# EgyptATTINY44.net
KiCad netlist of a schematic drawn in EAGLE
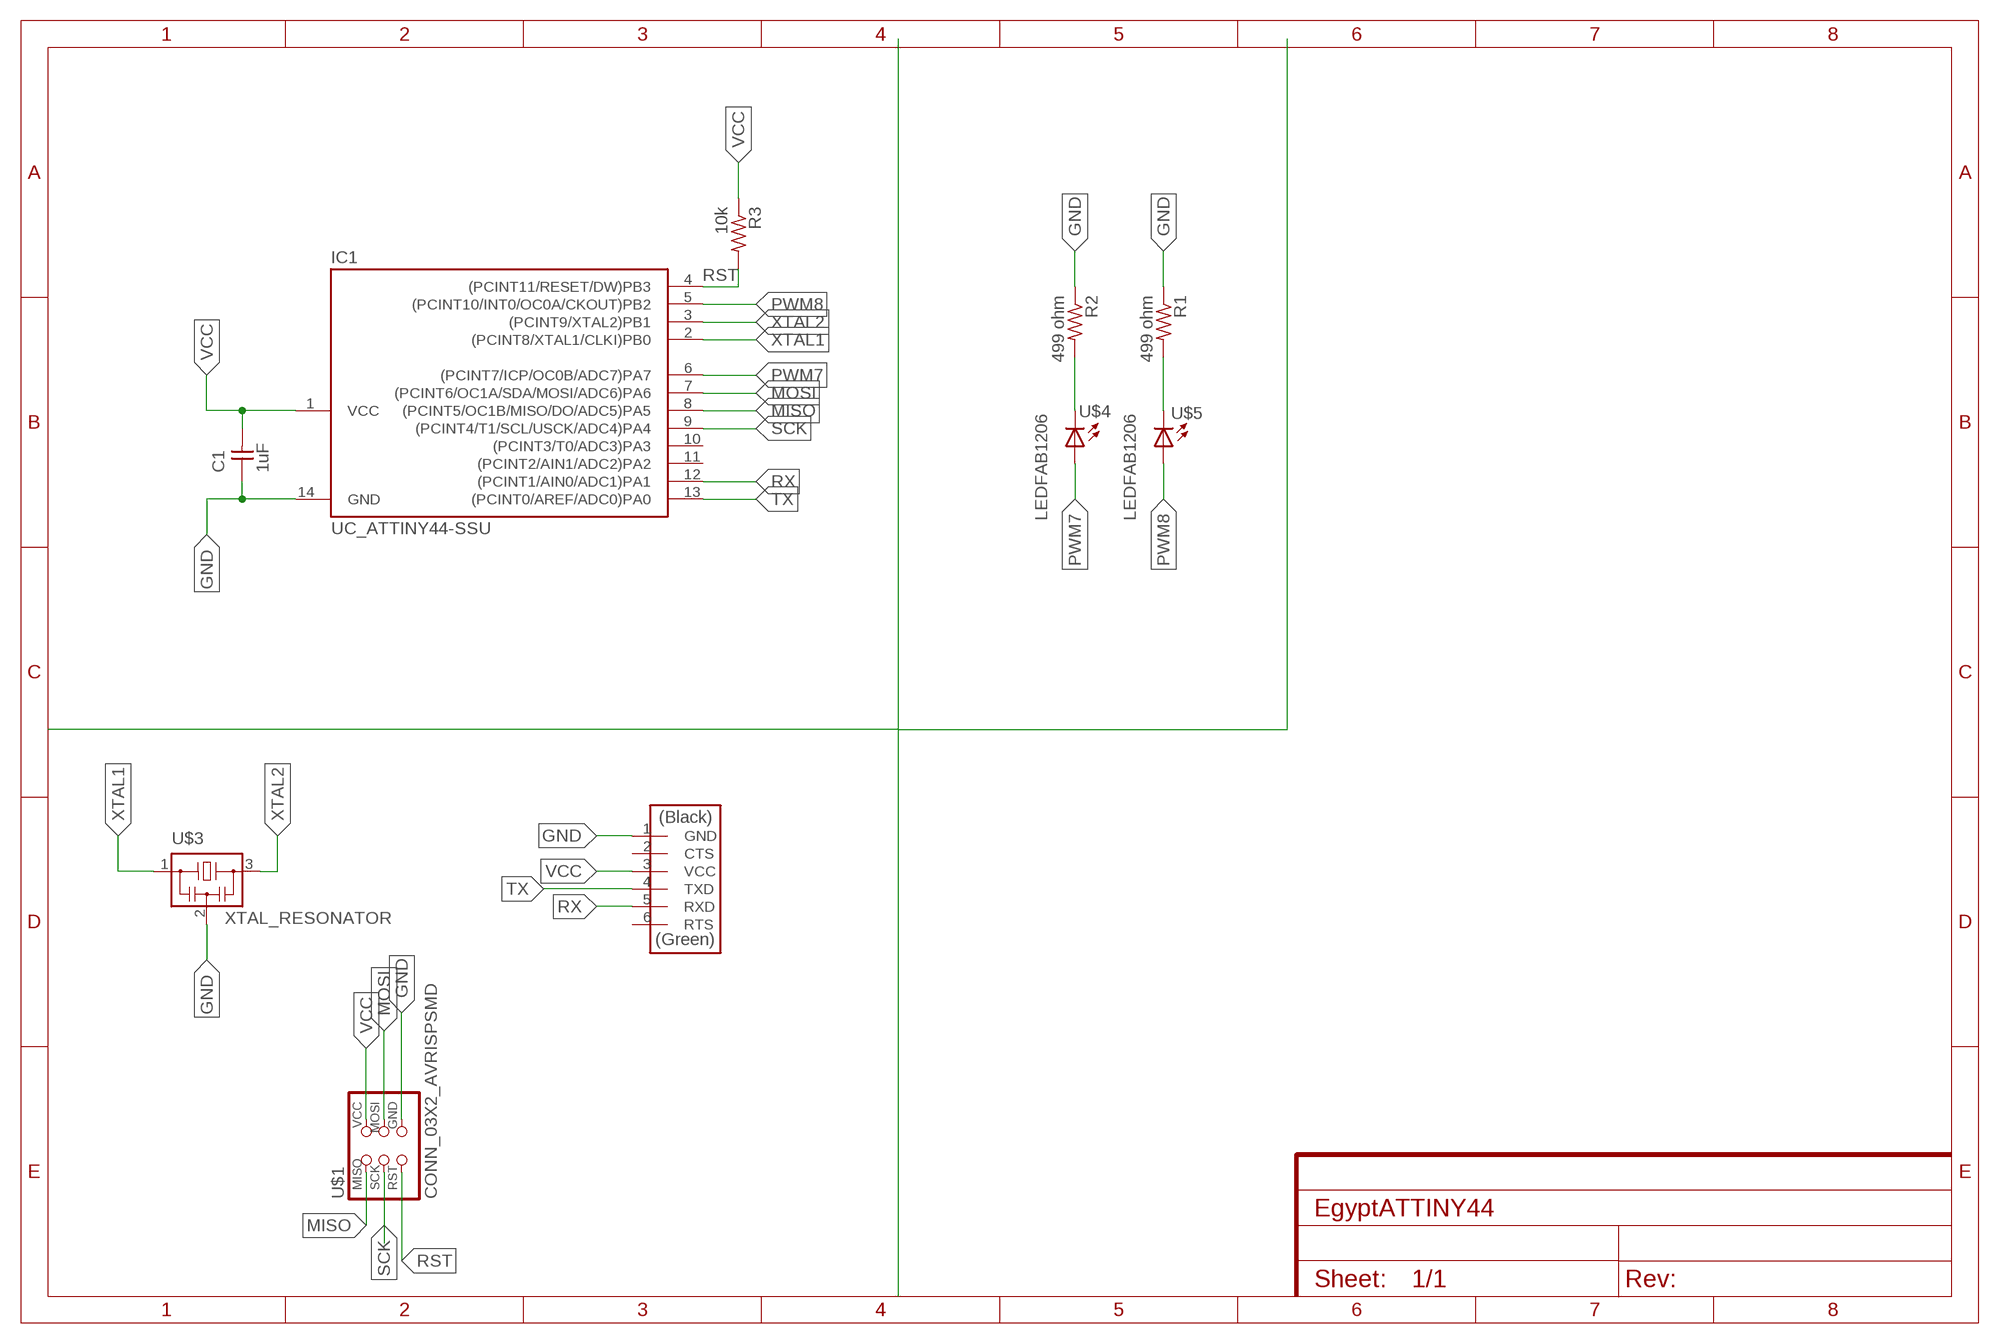
[diagram p0: schematic, sheet 1]

(export (version "E")
  (design (tool "Eeschema 10.0.6"))
  (components
    (comp (ref "C1")
      (value "1uF")
      (footprint "eagle-import:C1206FAB")
      (libsource (lib "eagle-import") (part "CAP_UNPOLARIZEDFAB"))
    )
    (comp (ref "IC1")
      (value "UC_ATTINY44-SSU")
      (footprint "eagle-import:SOIC14")
      (libsource (lib "eagle-import") (part "UC_ATTINY44-SSU"))
    )
    (comp (ref "R1")
      (value "499 ohm")
      (footprint "eagle-import:R1206FAB")
      (libsource (lib "eagle-import") (part "R1206FAB"))
    )
    (comp (ref "R2")
      (value "499 ohm")
      (footprint "eagle-import:R1206FAB")
      (libsource (lib "eagle-import") (part "R1206FAB"))
    )
    (comp (ref "R3")
      (value "10k")
      (footprint "eagle-import:R1206FAB")
      (libsource (lib "eagle-import") (part "R1206FAB"))
    )
    (comp (ref "U$1")
      (value "CONN_03X2_AVRISPSMD")
      (footprint "eagle-import:2X03SMD")
      (libsource (lib "eagle-import") (part "CONN_03X2_AVRISPSMD"))
    )
    (comp (ref "U$2")
      (value "CONN_06_FTDI-SMD-HEADER")
      (footprint "eagle-import:1X06SMD")
      (libsource (lib "eagle-import") (part "CONN_06_FTDI-SMD-HEADER"))
    )
    (comp (ref "U$3")
      (value "XTAL_RESONATOR")
      (footprint "eagle-import:EFOBM")
      (libsource (lib "eagle-import") (part "XTAL_RESONATOR"))
    )
    (comp (ref "U$4")
      (value "LEDFAB1206")
      (footprint "eagle-import:LED1206FAB")
      (libsource (lib "eagle-import") (part "LEDFAB1206"))
    )
    (comp (ref "U$5")
      (value "LEDFAB1206")
      (footprint "eagle-import:LED1206FAB")
      (libsource (lib "eagle-import") (part "LEDFAB1206"))
    )
  )
  (nets
    (net (code "1") (name "GND") (class "Default")
      (node (ref "C1") (pin "1") (pinfunction "1_1") (pintype "passive"))
      (node (ref "IC1") (pin "14") (pinfunction "GND_14") (pintype "power_in"))
      (node (ref "R1") (pin "1") (pinfunction "1_1") (pintype "passive"))
      (node (ref "R2") (pin "1") (pinfunction "1_1") (pintype "passive"))
      (node (ref "U$1") (pin "6") (pinfunction "GND_6") (pintype "passive"))
      (node (ref "U$2") (pin "1") (pinfunction "GND_1") (pintype "bidirectional"))
      (node (ref "U$3") (pin "2") (pinfunction "2_2") (pintype "passive"))
    )
    (net (code "2") (name "MISO") (class "Default")
      (node (ref "IC1") (pin "8") (pinfunction "(PCINT5/OC1B/MISO/DO/ADC5)PA5_8") (pintype "bidirectional"))
      (node (ref "U$1") (pin "1") (pinfunction "MISO_1") (pintype "passive"))
    )
    (net (code "3") (name "MOSI") (class "Default")
      (node (ref "IC1") (pin "7") (pinfunction "(PCINT6/OC1A/SDA/MOSI/ADC6)PA6_7") (pintype "bidirectional"))
      (node (ref "U$1") (pin "4") (pinfunction "MOSI_4") (pintype "passive"))
    )
    (net (code "4") (name "Net-(U$4-C)") (class "Default")
      (node (ref "R2") (pin "2") (pinfunction "2_2") (pintype "passive"))
      (node (ref "U$4") (pin "2") (pinfunction "C_2") (pintype "passive"))
    )
    (net (code "5") (name "Net-(U$5-C)") (class "Default")
      (node (ref "R1") (pin "2") (pinfunction "2_2") (pintype "passive"))
      (node (ref "U$5") (pin "2") (pinfunction "C_2") (pintype "passive"))
    )
    (net (code "6") (name "PWM7") (class "Default")
      (node (ref "IC1") (pin "6") (pinfunction "(PCINT7/ICP/OC0B/ADC7)PA7_6") (pintype "bidirectional"))
      (node (ref "U$4") (pin "1") (pinfunction "A_1") (pintype "passive"))
    )
    (net (code "7") (name "PWM8") (class "Default")
      (node (ref "IC1") (pin "5") (pinfunction "(PCINT10/INT0/OC0A/CKOUT)PB2_5") (pintype "bidirectional"))
      (node (ref "U$5") (pin "1") (pinfunction "A_1") (pintype "passive"))
    )
    (net (code "8") (name "RST") (class "Default")
      (node (ref "IC1") (pin "4") (pinfunction "(PCINT11/RESET/DW)PB3_4") (pintype "bidirectional"))
      (node (ref "R3") (pin "2") (pinfunction "2_2") (pintype "passive"))
      (node (ref "U$1") (pin "5") (pinfunction "RST_5") (pintype "passive"))
    )
    (net (code "9") (name "RX") (class "Default")
      (node (ref "IC1") (pin "12") (pinfunction "(PCINT1/AIN0/ADC1)PA1_12") (pintype "bidirectional"))
      (node (ref "U$2") (pin "5") (pinfunction "RXD_5") (pintype "bidirectional"))
    )
    (net (code "10") (name "SCK") (class "Default")
      (node (ref "IC1") (pin "9") (pinfunction "(PCINT4/T1/SCL/USCK/ADC4)PA4_9") (pintype "bidirectional"))
      (node (ref "U$1") (pin "3") (pinfunction "SCK_3") (pintype "passive"))
    )
    (net (code "11") (name "TX") (class "Default")
      (node (ref "IC1") (pin "13") (pinfunction "(PCINT0/AREF/ADC0)PA0_13") (pintype "bidirectional"))
      (node (ref "U$2") (pin "4") (pinfunction "TXD_4") (pintype "bidirectional"))
    )
    (net (code "12") (name "VCC") (class "Default")
      (node (ref "C1") (pin "2") (pinfunction "2_2") (pintype "passive"))
      (node (ref "IC1") (pin "1") (pinfunction "VCC_1") (pintype "power_in"))
      (node (ref "R3") (pin "1") (pinfunction "1_1") (pintype "passive"))
      (node (ref "U$1") (pin "2") (pinfunction "VCC_2") (pintype "passive"))
      (node (ref "U$2") (pin "3") (pinfunction "VCC_3") (pintype "bidirectional"))
    )
    (net (code "13") (name "XTAL1") (class "Default")
      (node (ref "IC1") (pin "2") (pinfunction "(PCINT8/XTAL1/CLKI)PB0_2") (pintype "bidirectional"))
      (node (ref "U$3") (pin "1") (pinfunction "1_1") (pintype "passive"))
    )
    (net (code "14") (name "XTAL2") (class "Default")
      (node (ref "IC1") (pin "3") (pinfunction "(PCINT9/XTAL2)PB1_3") (pintype "bidirectional"))
      (node (ref "U$3") (pin "3") (pinfunction "3_3") (pintype "passive"))
    )
    (net (code "15") (name "unconnected-(IC1-(PCINT2{slash}AIN1{slash}ADC2)PA2-Pad11)") (class "Default")
      (node (ref "IC1") (pin "11") (pinfunction "(PCINT2/AIN1/ADC2)PA2_11") (pintype "bidirectional"))
    )
    (net (code "16") (name "unconnected-(IC1-(PCINT3{slash}T0{slash}ADC3)PA3-Pad10)") (class "Default")
      (node (ref "IC1") (pin "10") (pinfunction "(PCINT3/T0/ADC3)PA3_10") (pintype "bidirectional"))
    )
    (net (code "17") (name "unconnected-(U$2-CTS-Pad2)") (class "Default")
      (node (ref "U$2") (pin "2") (pinfunction "CTS_2") (pintype "bidirectional"))
    )
    (net (code "18") (name "unconnected-(U$2-RTS-Pad6)") (class "Default")
      (node (ref "U$2") (pin "6") (pinfunction "RTS_6") (pintype "bidirectional"))
    )
  )
)
